# obc-v2_DEBUG.net
KiCad netlist of a schematic drawn in Altium Designer
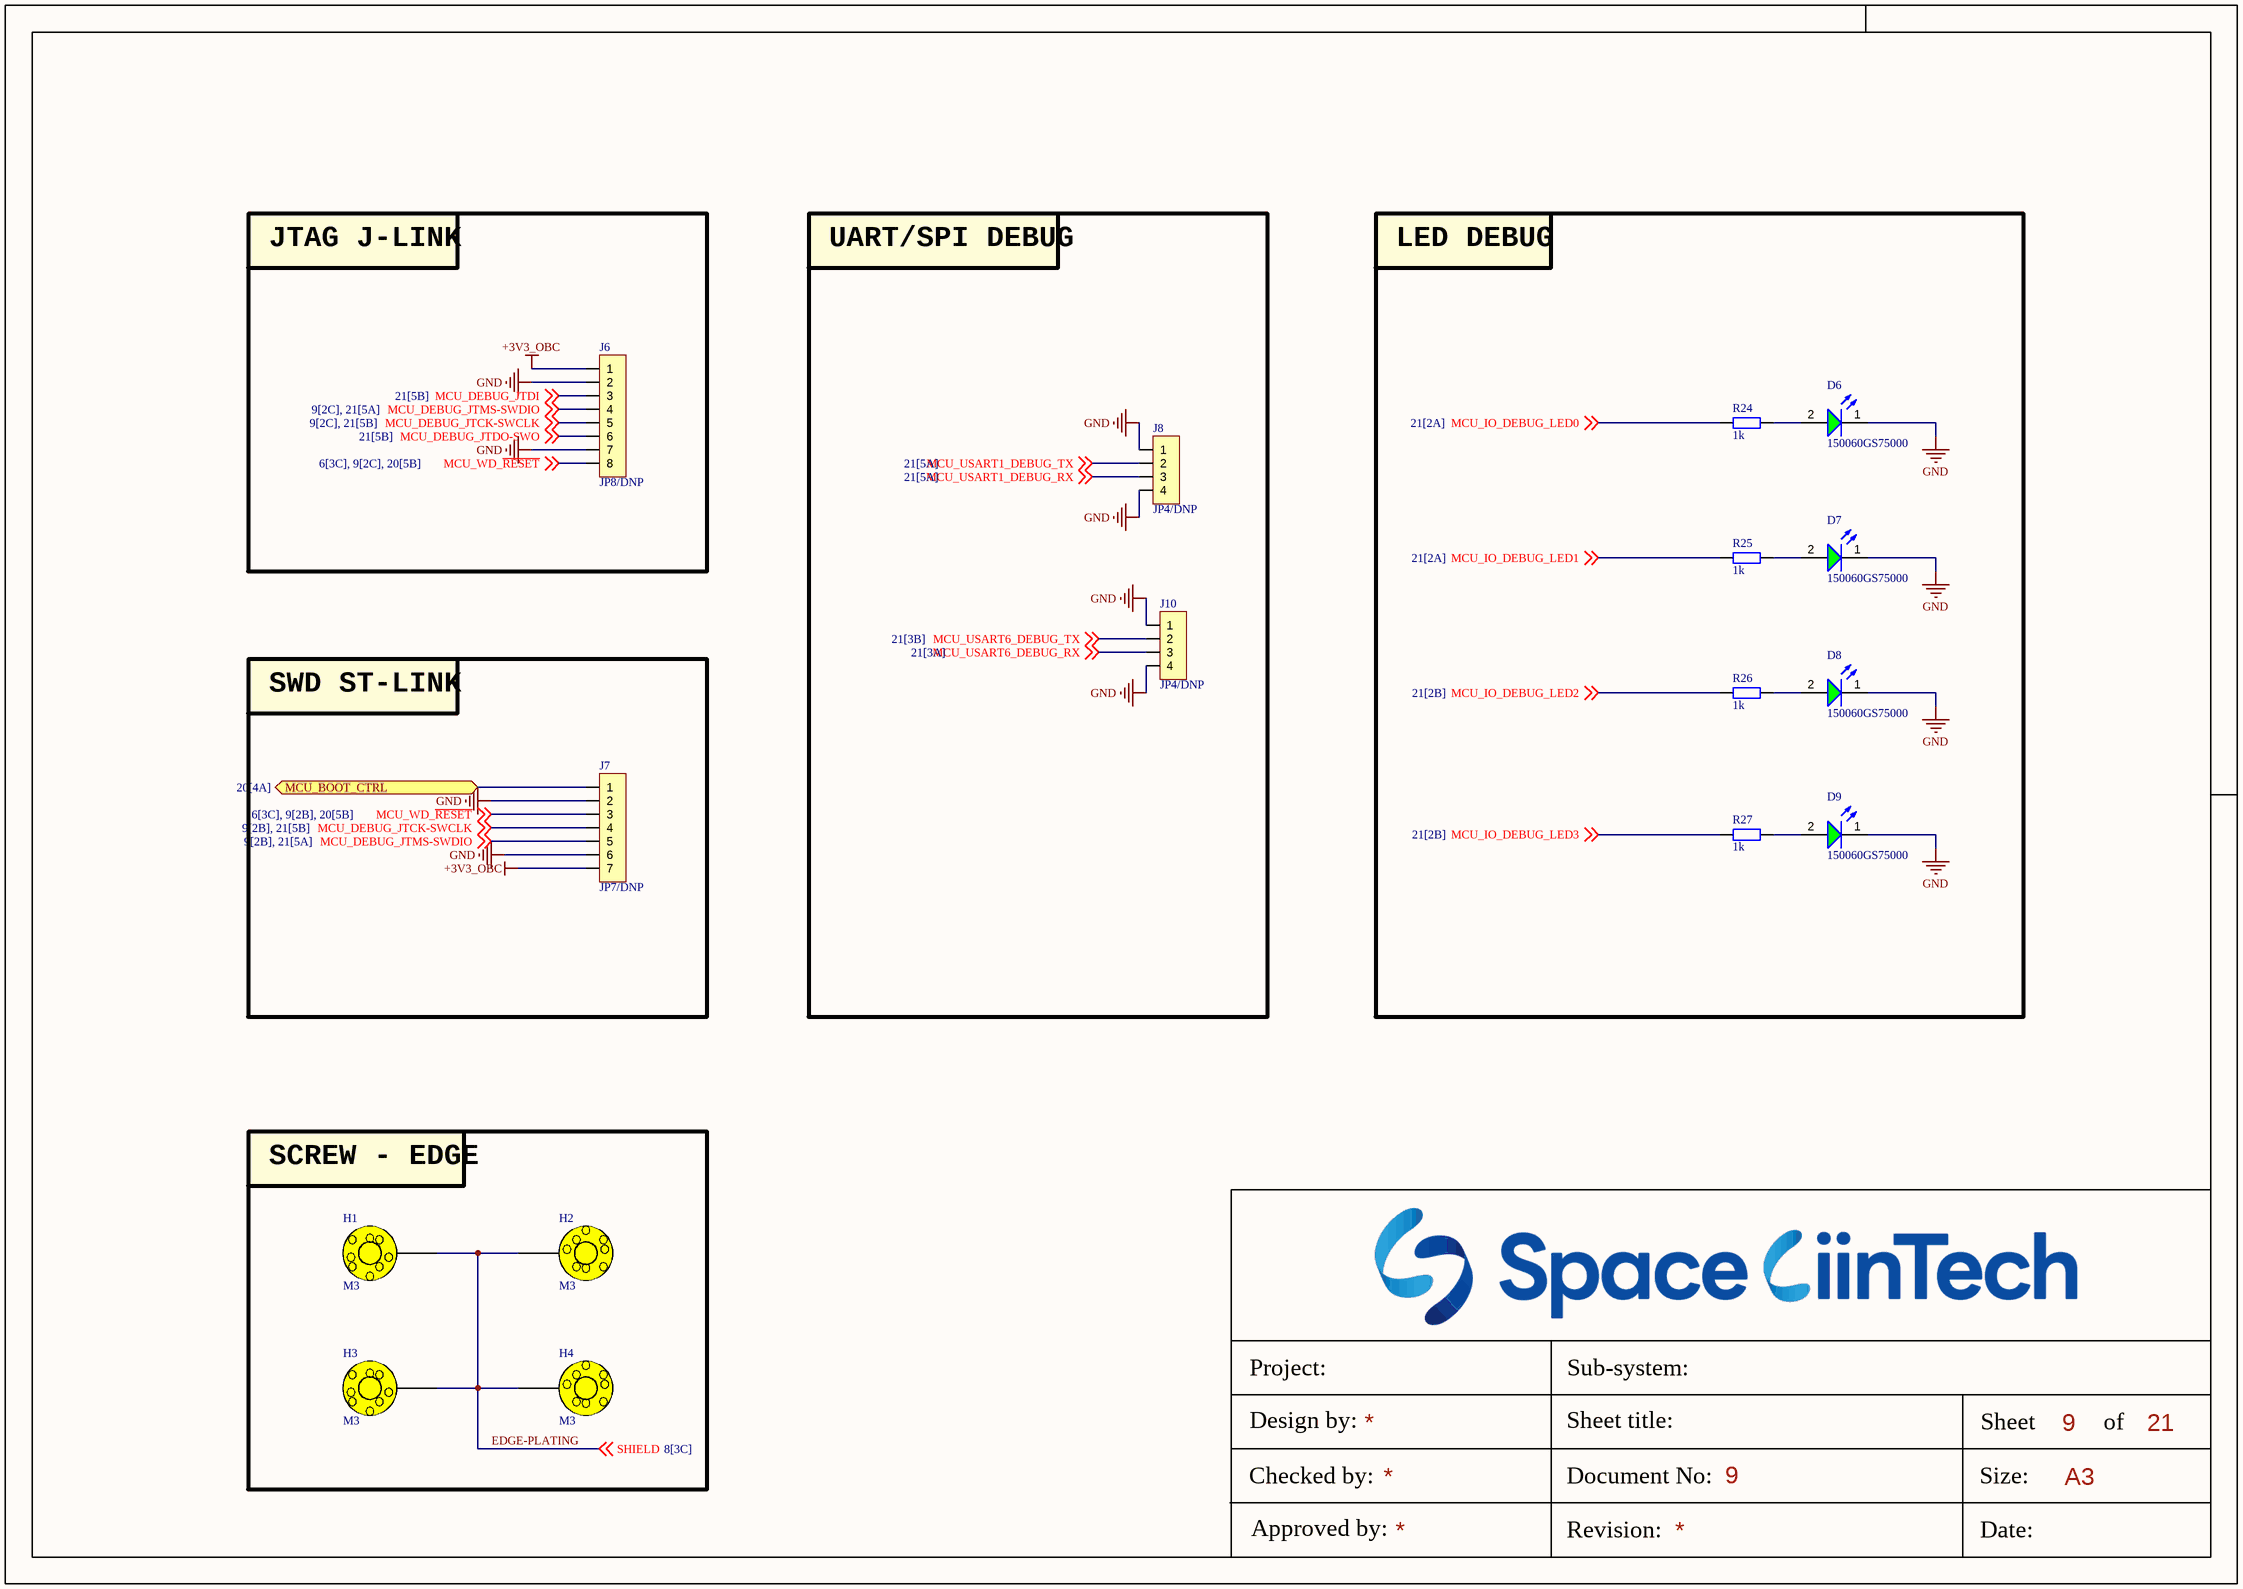
[diagram p0: obc-v2_DEBUG.SchDoc]

(export (version "E")
  (design (tool "Eeschema 10.0.6"))
  (components
    (comp (ref "D6")
      (value "150060GS75000")
      (footprint "WL-SMCW_0603_150060xx75000")
      (description "430mcd Colorless transparence 520nm Emerald 140° LED0603 Light Emitting Diodes (LED) ROHS")
      (libsource (lib "Altium Content Vault") (part "LED_Green_2A-1K"))
    )
    (comp (ref "D7")
      (value "150060GS75000")
      (footprint "WL-SMCW_0603_150060xx75000")
      (description "430mcd Colorless transparence 520nm Emerald 140° LED0603 Light Emitting Diodes (LED) ROHS")
      (libsource (lib "Altium Content Vault") (part "LED_Green_2A-1K"))
    )
    (comp (ref "D8")
      (value "150060GS75000")
      (footprint "WL-SMCW_0603_150060xx75000")
      (description "430mcd Colorless transparence 520nm Emerald 140° LED0603 Light Emitting Diodes (LED) ROHS")
      (libsource (lib "Altium Content Vault") (part "LED_Green_2A-1K"))
    )
    (comp (ref "D9")
      (value "150060GS75000")
      (footprint "WL-SMCW_0603_150060xx75000")
      (description "430mcd Colorless transparence 520nm Emerald 140° LED0603 Light Emitting Diodes (LED) ROHS")
      (libsource (lib "Altium Content Vault") (part "LED_Green_2A-1K"))
    )
    (comp (ref "H1") (value "M3") (footprint "HEX-M3") (libsource (lib "hex_M3") (part "HEX-M3")))
    (comp (ref "H2") (value "M3") (footprint "HEX-M3") (libsource (lib "hex_M3") (part "HEX-M3")))
    (comp (ref "H3") (value "M3") (footprint "HEX-M3") (libsource (lib "hex_M3") (part "HEX-M3")))
    (comp (ref "H4") (value "M3") (footprint "HEX-M3") (libsource (lib "hex_M3") (part "HEX-M3")))
    (comp (ref "J6") (value "JP8/DNP") (footprint "JP8-C1T") (libsource (lib "obc_ver2") (part "JP8")))
    (comp (ref "J7") (value "JP7/DNP") (footprint "JP7-C1T") (libsource (lib "obc_ver2") (part "JP7")))
    (comp (ref "J8")
      (value "JP4/DNP")
      (footprint "JP4-C1T")
      (description "WR-PHD 2.54 mm Angled Socket Header")
      (fields
        (field (name "MANUFACTURER") "Würth Elektronik eiSos GmbH")
        (field (name "PARTNO") "613004143121")
        (field (name "CREATED BY") "Karrer Zheng")
      )
      (libsource (lib "TechMT.VN_Lib_Project v2") (part "JP4"))
    )
    (comp (ref "J10")
      (value "JP4/DNP")
      (footprint "JP4-C1T")
      (description "WR-PHD 2.54 mm Angled Socket Header")
      (fields
        (field (name "MANUFACTURER") "Würth Elektronik eiSos GmbH")
        (field (name "PARTNO") "613004143121")
        (field (name "CREATED BY") "Karrer Zheng")
      )
      (libsource (lib "TechMT.VN_Lib_Project v2") (part "JP4"))
    )
    (comp (ref "R24")
      (value "1k")
      (footprint "RES_C_1608X60")
      (description "RES")
      (libsource (lib "Altium_Lib_by_KhueNguyenCreator") (part "Tro 0603 1% 10k"))
    )
    (comp (ref "R25")
      (value "1k")
      (footprint "RES_C_1608X60")
      (description "RES")
      (libsource (lib "Altium_Lib_by_KhueNguyenCreator") (part "Tro 0603 1% 10k"))
    )
    (comp (ref "R26")
      (value "1k")
      (footprint "RES_C_1608X60")
      (description "RES")
      (libsource (lib "Altium_Lib_by_KhueNguyenCreator") (part "Tro 0603 1% 10k"))
    )
    (comp (ref "R27")
      (value "1k")
      (footprint "RES_C_1608X60")
      (description "RES")
      (libsource (lib "Altium_Lib_by_KhueNguyenCreator") (part "Tro 0603 1% 10k"))
    )
  )
  (nets
    (net (code "1") (name "+3V3_OBC") (class "Default")
      (node (ref "J6") (pin "1") (pinfunction "1_1") (pintype "passive"))
      (node (ref "J7") (pin "7") (pinfunction "7_7") (pintype "passive"))
    )
    (net (code "2") (name "/MCU_BOOT_CTRL") (class "Default")
      (node (ref "J7") (pin "1") (pinfunction "1_1") (pintype "passive"))
    )
    (net (code "3") (name "GND") (class "Default")
      (node (ref "D6") (pin "1") (pinfunction "K_1") (pintype "passive"))
      (node (ref "D7") (pin "1") (pinfunction "K_1") (pintype "passive"))
      (node (ref "D8") (pin "1") (pinfunction "K_1") (pintype "passive"))
      (node (ref "D9") (pin "1") (pinfunction "K_1") (pintype "passive"))
      (node (ref "J10") (pin "1") (pinfunction "1_1") (pintype "passive"))
      (node (ref "J10") (pin "4") (pinfunction "4_4") (pintype "passive"))
      (node (ref "J6") (pin "2") (pinfunction "2_2") (pintype "passive"))
      (node (ref "J6") (pin "7") (pinfunction "7_7") (pintype "passive"))
      (node (ref "J7") (pin "2") (pinfunction "2_2") (pintype "passive"))
      (node (ref "J7") (pin "6") (pinfunction "6_6") (pintype "passive"))
      (node (ref "J8") (pin "1") (pinfunction "1_1") (pintype "passive"))
      (node (ref "J8") (pin "4") (pinfunction "4_4") (pintype "passive"))
    )
    (net (code "4") (name "MCU_DEBUG_JTCK-SWCLK") (class "Default")
      (node (ref "J6") (pin "5") (pinfunction "5_5") (pintype "passive"))
      (node (ref "J7") (pin "4") (pinfunction "4_4") (pintype "passive"))
    )
    (net (code "5") (name "MCU_DEBUG_JTDI") (class "Default")
      (node (ref "J6") (pin "3") (pinfunction "3_3") (pintype "passive"))
    )
    (net (code "6") (name "MCU_DEBUG_JTDO-SWO") (class "Default")
      (node (ref "J6") (pin "6") (pinfunction "6_6") (pintype "passive"))
    )
    (net (code "7") (name "MCU_DEBUG_JTMS-SWDIO") (class "Default")
      (node (ref "J6") (pin "4") (pinfunction "4_4") (pintype "passive"))
      (node (ref "J7") (pin "5") (pinfunction "5_5") (pintype "passive"))
    )
    (net (code "8") (name "MCU_IO_DEBUG_LED0") (class "Default")
      (node (ref "R24") (pin "2") (pinfunction "2_2") (pintype "passive"))
    )
    (net (code "9") (name "MCU_IO_DEBUG_LED1") (class "Default")
      (node (ref "R25") (pin "2") (pinfunction "2_2") (pintype "passive"))
    )
    (net (code "10") (name "MCU_IO_DEBUG_LED2") (class "Default")
      (node (ref "R26") (pin "2") (pinfunction "2_2") (pintype "passive"))
    )
    (net (code "11") (name "MCU_IO_DEBUG_LED3") (class "Default")
      (node (ref "R27") (pin "2") (pinfunction "2_2") (pintype "passive"))
    )
    (net (code "12") (name "MCU_USART1_DEBUG_RX") (class "Default")
      (node (ref "J8") (pin "3") (pinfunction "3_3") (pintype "passive"))
    )
    (net (code "13") (name "MCU_USART1_DEBUG_TX") (class "Default")
      (node (ref "J8") (pin "2") (pinfunction "2_2") (pintype "passive"))
    )
    (net (code "14") (name "MCU_USART6_DEBUG_RX") (class "Default")
      (node (ref "J10") (pin "3") (pinfunction "3_3") (pintype "passive"))
    )
    (net (code "15") (name "MCU_USART6_DEBUG_TX") (class "Default")
      (node (ref "J10") (pin "2") (pinfunction "2_2") (pintype "passive"))
    )
    (net (code "16") (name "MCU_WD_~{RESET}") (class "Default")
      (node (ref "J6") (pin "8") (pinfunction "8_8") (pintype "passive"))
      (node (ref "J7") (pin "3") (pinfunction "3_3") (pintype "passive"))
    )
    (net (code "17") (name "Net-(D6-A)") (class "Default")
      (node (ref "D6") (pin "2") (pinfunction "A_2") (pintype "passive"))
      (node (ref "R24") (pin "1") (pinfunction "1_1") (pintype "passive"))
    )
    (net (code "18") (name "Net-(D7-A)") (class "Default")
      (node (ref "D7") (pin "2") (pinfunction "A_2") (pintype "passive"))
      (node (ref "R25") (pin "1") (pinfunction "1_1") (pintype "passive"))
    )
    (net (code "19") (name "Net-(D8-A)") (class "Default")
      (node (ref "D8") (pin "2") (pinfunction "A_2") (pintype "passive"))
      (node (ref "R26") (pin "1") (pinfunction "1_1") (pintype "passive"))
    )
    (net (code "20") (name "Net-(D9-A)") (class "Default")
      (node (ref "D9") (pin "2") (pinfunction "A_2") (pintype "passive"))
      (node (ref "R27") (pin "1") (pinfunction "1_1") (pintype "passive"))
    )
    (net (code "21") (name "SHIELD") (class "Default")
      (node (ref "H1") (pin "1") (pinfunction "1_1") (pintype "power_in"))
      (node (ref "H2") (pin "1") (pinfunction "1_1") (pintype "power_in"))
      (node (ref "H3") (pin "1") (pinfunction "1_1") (pintype "power_in"))
      (node (ref "H4") (pin "1") (pinfunction "1_1") (pintype "power_in"))
    )
  )
)
